# Charger_Indicator.net
KiCad netlist of a schematic drawn in EAGLE
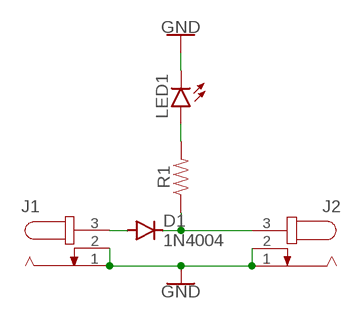
[diagram p0: schematic, sheet 1]

(export (version "E")
  (design (tool "Eeschema 10.0.6"))
  (components
    (comp (ref "D1")
      (value "1N4004")
      (footprint "eagle-import:DO41-10")
      (libsource (lib "eagle-import") (part "1N4004"))
    )
    (comp (ref "J1")
      (value "JACK-PLUG0")
      (footprint "eagle-import:SPC4077")
      (libsource (lib "eagle-import") (part "JACK-PLUG0"))
    )
    (comp (ref "J2")
      (value "JACK-PLUG0")
      (footprint "eagle-import:SPC4077")
      (libsource (lib "eagle-import") (part "JACK-PLUG0"))
    )
    (comp (ref "LED1")
      (value "LED3MM")
      (footprint "eagle-import:LED3MM")
      (libsource (lib "eagle-import") (part "LED3MM"))
    )
    (comp (ref "R1")
      (value "RESISTOR1206")
      (footprint "eagle-import:1206")
      (libsource (lib "eagle-import") (part "RESISTOR1206"))
    )
  )
  (nets
    (net (code "1") (name "GND") (class "Default")
      (node (ref "J1") (pin "1") (pinfunction "1_1") (pintype "passive"))
      (node (ref "J1") (pin "2") (pinfunction "2_2") (pintype "passive"))
      (node (ref "J2") (pin "1") (pinfunction "1_1") (pintype "passive"))
      (node (ref "J2") (pin "2") (pinfunction "2_2") (pintype "passive"))
      (node (ref "LED1") (pin "K") (pinfunction "C_K") (pintype "passive"))
    )
    (net (code "2") (name "Net-(D1-PadA)") (class "Default")
      (node (ref "D1") (pin "A") (pinfunction "A_A") (pintype "passive"))
      (node (ref "J1") (pin "3") (pinfunction "3_3") (pintype "passive"))
    )
    (net (code "3") (name "Net-(D1-PadC)") (class "Default")
      (node (ref "D1") (pin "C") (pinfunction "C_C") (pintype "passive"))
      (node (ref "J2") (pin "3") (pinfunction "3_3") (pintype "passive"))
      (node (ref "R1") (pin "1") (pinfunction "1_1") (pintype "passive"))
    )
    (net (code "4") (name "Net-(LED1-PadA)") (class "Default")
      (node (ref "LED1") (pin "A") (pinfunction "A_A") (pintype "passive"))
      (node (ref "R1") (pin "2") (pinfunction "2_2") (pintype "passive"))
    )
  )
)
